# DIOT_Power_Supplies.net
KiCad netlist of a schematic drawn in Altium Designer
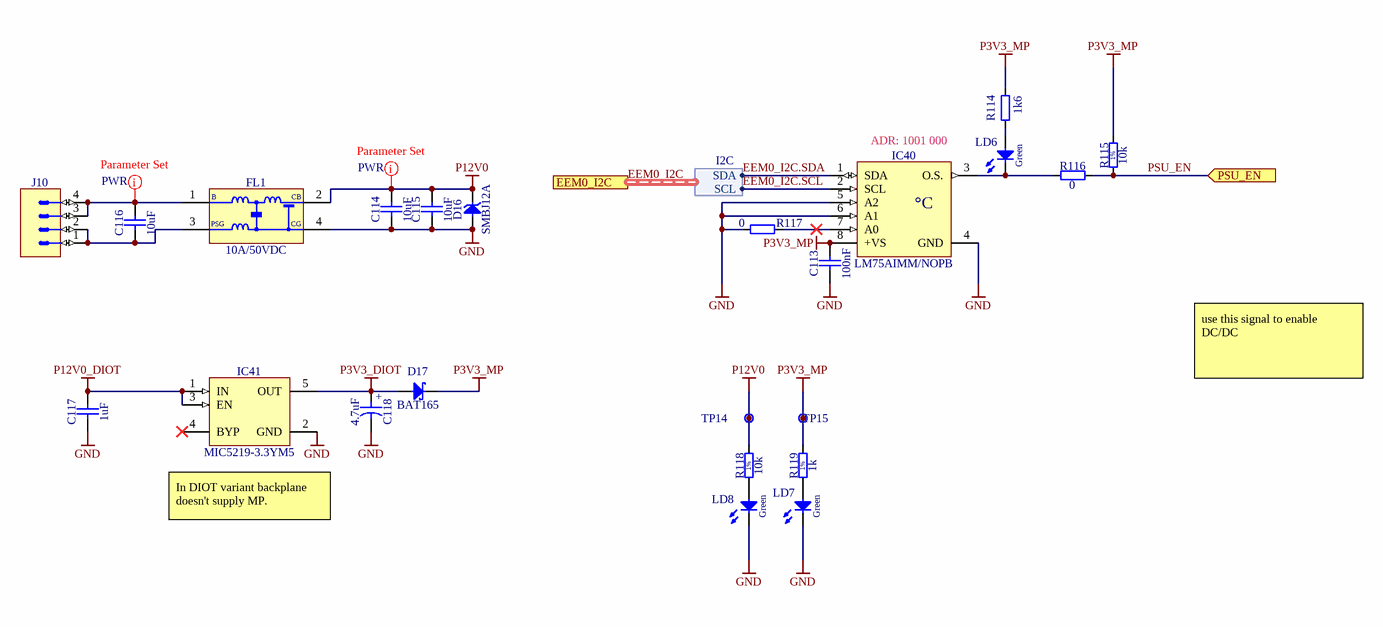
[diagram p0: DIOT_Power_Supplies.SchDoc]

(export (version "E")
  (design (tool "Eeschema 10.0.6"))
  (components
    (comp (ref "C113")
      (value "100nF")
      (footprint "CAPC1005X55N")
      (description "Non-polarised capacitor")
      (fields
        (field (name "PART NUMBER") "CC0402_100NF_16V_10%_X5R")
        (field (name "VOLTAGE") "16V")
        (field (name "AUTHOR") "CERN DEM JLC")
      )
      (libsource (lib "Capacitors") (part "Capacitor - non polarized"))
    )
    (comp (ref "C114")
      (value "10uF")
      (footprint "CAPC2012X95N")
      (description "Non-polarised capacitor")
      (fields
        (field (name "PART NUMBER") "CC0805_10UF_25V_10%_X5R")
        (field (name "VOLTAGE") "25V")
        (field (name "AUTHOR") "CERN DEM JLC")
      )
      (libsource (lib "Capacitors") (part "Capacitor - non polarized"))
    )
    (comp (ref "C115")
      (value "10uF")
      (footprint "CAPC2012X95N")
      (description "Non-polarised capacitor")
      (fields
        (field (name "PART NUMBER") "CC0805_10UF_25V_10%_X5R")
        (field (name "VOLTAGE") "25V")
        (field (name "AUTHOR") "CERN DEM JLC")
      )
      (libsource (lib "Capacitors") (part "Capacitor - non polarized"))
    )
    (comp (ref "C116")
      (value "10uF")
      (footprint "CAPC2012X95N")
      (description "Non-polarised capacitor")
      (fields
        (field (name "PART NUMBER") "CC0805_10UF_25V_10%_X5R")
        (field (name "VOLTAGE") "25V")
        (field (name "AUTHOR") "CERN DEM JLC")
      )
      (libsource (lib "Capacitors") (part "Capacitor - non polarized"))
    )
    (comp (ref "C117")
      (value "1uF")
      (footprint "CAPC1608X87N")
      (description "Non-polarised capacitor")
      (fields
        (field (name "PART NUMBER") "CC0603_1UF_25V_10%_X7R")
        (field (name "VOLTAGE") "25V")
        (field (name "AUTHOR") "CERN DEM JLC")
      )
      (libsource (lib "Capacitors") (part "Capacitor - non polarized"))
    )
    (comp (ref "C118")
      (value "4.7uF")
      (footprint "CAPMP3216X180N")
      (description "Polarised capacitor")
      (fields
        (field (name "PART NUMBER") "CTE3216-18_4.7UF_10V_10%_AVX_TPSA475K010T1400")
        (field (name "VOLTAGE") "10V")
        (field (name "AUTHOR") "CERN DEM JLC")
      )
      (libsource (lib "Capacitors") (part "Capacitor - polarized"))
    )
    (comp (ref "D16")
      (value "SMBJ12A")
      (footprint "DIOM5336X265N")
      (description "Zener Diode")
      (fields
        (field (name "VOLTAGE") "12V")
        (field (name "POWER") "600W")
        (field (name "AUTHOR") "CERN DEM JLC")
      )
      (libsource (lib "ICs And Semiconductors") (part "Diode Zener"))
    )
    (comp (ref "D17")
      (value "BAT165")
      (footprint "SOD2512X110N")
      (description "Schottky Diode")
      (fields
        (field (name "MANUFACTURER") "INFINEON")
        (field (name "VOLTAGE") "40V")
        (field (name "AUTHOR") "CERN DEM JLC")
      )
      (libsource (lib "ICs And Semiconductors") (part "Diode Schottky"))
    )
    (comp (ref "FL1")
      (value "10A/50VDC")
      (footprint "FIL_MURATA_BNX02")
      (description "Block Type EMIFIL (LC Combined)")
      (fields
        (field (name "PART NUMBER") "FIL_MURATA_BNX022-01L")
        (field (name "MANUFACTURER") "MURATA")
        (field (name "AUTHOR") "CERN DEM JLC")
      )
      (libsource (lib "Inductors & Transformers") (part "FIL_MURATA_BNX02"))
    )
    (comp (ref "IC40")
      (value "LM75AIMM/NOPB")
      (footprint "SOP65P490X109-8N")
      (description "Digital Temperature Sensor and Thermal Watchdog with Two-Wire Interface")
      (fields (field (name "MANUFACTURER") "TEXAS INSTRUMENTS") (field (name "AUTHOR") "CERN DEM JLC"))
      (libsource (lib "ICs And Semiconductors") (part "LM75"))
    )
    (comp (ref "IC41")
      (value "MIC5219-3.3YM5")
      (footprint "SOT95P280X145-5N")
      (description "500mA Peak Output LDO Regulator")
      (fields (field (name "MANUFACTURER") "MICROCHIP TECHNOLOGY") (field (name "AUTHOR") "CERN DEM WB"))
      (libsource (lib "ICs And Semiconductors") (part "MIC5219-X.XYM5"))
    )
    (comp (ref "J10")
      (value "Mini-Fit Jr.™")
      (footprint "MOLEX_39-30-0040")
      (description "Connector 4 Male")
      (fields
        (field (name "PART NUMBER") "MOLEX_39-30-0040")
        (field (name "MANUFACTURER") "MOLEX")
        (field (name "AUTHOR") "CERN DEM JLC")
      )
      (libsource (lib "Connectors") (part "Connector 4 Male"))
    )
    (comp (ref "LD6")
      (value "Green")
      (footprint "LED_KINGBRIGHT_KPH-1608CGCK")
      (description "LED Green 1C 2A")
      (fields
        (field (name "MANUFACTURER PART NUMBER") "KPH-1608CGCK")
        (field (name "PART NUMBER") "LED_KINGBRIGHT_KPH-1608CGCK")
        (field (name "AUTHOR") "CERN DEM JLC")
      )
      (libsource (lib "ICs And Semiconductors") (part "LED Green 1C 2A"))
    )
    (comp (ref "LD7")
      (value "Green")
      (footprint "LED_KINGBRIGHT_KPH-1608CGCK")
      (description "LED Green 1C 2A")
      (fields
        (field (name "MANUFACTURER PART NUMBER") "KPH-1608CGCK")
        (field (name "PART NUMBER") "LED_KINGBRIGHT_KPH-1608CGCK")
        (field (name "AUTHOR") "CERN DEM JLC")
      )
      (libsource (lib "ICs And Semiconductors") (part "LED Green 1C 2A"))
    )
    (comp (ref "LD8")
      (value "Green")
      (footprint "LED_KINGBRIGHT_KPH-1608CGCK")
      (description "LED Green 1C 2A")
      (fields
        (field (name "MANUFACTURER PART NUMBER") "KPH-1608CGCK")
        (field (name "PART NUMBER") "LED_KINGBRIGHT_KPH-1608CGCK")
        (field (name "AUTHOR") "CERN DEM JLC")
      )
      (libsource (lib "ICs And Semiconductors") (part "LED Green 1C 2A"))
    )
    (comp (ref "R114")
      (value "1k6")
      (footprint "RESC1005X40N")
      (description "Resistor - 1%")
      (fields
        (field (name "PART NUMBER") "R0402_1K6_1%_0.0625W_100PPM")
        (field (name "POWER") "0.0625W")
        (field (name "AUTHOR") "CERN DEM JLC")
      )
      (libsource (lib "Resistors") (part "Resistor - 1%"))
    )
    (comp (ref "R115")
      (value "10k")
      (footprint "RESC1005X40N")
      (description "Resistor - 1%")
      (fields
        (field (name "PART NUMBER") "R0402_10K_1%_0.0625W_100PPM")
        (field (name "POWER") "0.0625W")
        (field (name "AUTHOR") "CERN DEM JLC")
      )
      (libsource (lib "Resistors") (part "Resistor - 1%"))
    )
    (comp (ref "R116")
      (value "0")
      (footprint "RESC1005X40N")
      (description "Resistor")
      (fields
        (field (name "PART NUMBER") "R0402_0R_JUMPER")
        (field (name "MANUFACTURER") "GENERIC")
        (field (name "AUTHOR") "CERN DEM JLC")
      )
      (libsource (lib "Resistors") (part "Resistor"))
    )
    (comp (ref "R117")
      (value "0")
      (footprint "RESC1005X40N")
      (description "Resistor")
      (fields
        (field (name "PART NUMBER") "R0402_0R_JUMPER")
        (field (name "MANUFACTURER") "GENERIC")
        (field (name "AUTHOR") "CERN DEM JLC")
      )
      (libsource (lib "Resistors") (part "Resistor"))
    )
    (comp (ref "R118")
      (value "10k")
      (footprint "RESC1005X40N")
      (description "Resistor - 1%")
      (fields
        (field (name "PART NUMBER") "R0402_10K_1%_0.0625W_100PPM")
        (field (name "POWER") "0.0625W")
        (field (name "AUTHOR") "CERN DEM JLC")
      )
      (libsource (lib "Resistors") (part "Resistor - 1%"))
    )
    (comp (ref "R119")
      (value "1k")
      (footprint "RESC1005X40N")
      (description "Resistor - 1%")
      (fields
        (field (name "PART NUMBER") "R0402_1K_1%_0.0625W_100PPM")
        (field (name "POWER") "0.0625W")
        (field (name "AUTHOR") "CERN DEM JLC")
      )
      (libsource (lib "Resistors") (part "Resistor - 1%"))
    )
    (comp (ref "TP14")
      (value "P12V0")
      (footprint "TPS127")
      (description "Test Point")
      (fields (field (name "PART NUMBER") "SMD_PAD_1.27X1.27MM") (field (name "AUTHOR") "CERN DEM JLC"))
      (libsource (lib "Eletro-mechanical") (part "Test Point"))
    )
    (comp (ref "TP15")
      (value "P3V3")
      (footprint "TPS127")
      (description "Test Point")
      (fields (field (name "PART NUMBER") "SMD_PAD_1.27X1.27MM") (field (name "AUTHOR") "CERN DEM JLC"))
      (libsource (lib "Eletro-mechanical") (part "Test Point"))
    )
  )
  (nets
    (net (code "2") (name "/EEM0_I2C.SCL") (class "Default")
      (node (ref "IC40") (pin "2") (pinfunction "SCL_2") (pintype "input"))
    )
    (net (code "3") (name "/EEM0_I2C.SDA") (class "Default")
      (node (ref "IC40") (pin "1") (pinfunction "SDA_1") (pintype "bidirectional"))
    )
    (net (code "5") (name "/PSU_EN") (class "Default")
      (node (ref "R115") (pin "1") (pinfunction "1_1") (pintype "passive"))
      (node (ref "R116") (pin "2") (pinfunction "2_2") (pintype "passive"))
    )
    (net (code "6") (name "GND") (class "Default")
      (node (ref "C113") (pin "1") (pinfunction "1_1") (pintype "passive"))
      (node (ref "C114") (pin "1") (pinfunction "1_1") (pintype "passive"))
      (node (ref "C115") (pin "1") (pinfunction "1_1") (pintype "passive"))
      (node (ref "C117") (pin "1") (pinfunction "1_1") (pintype "passive"))
      (node (ref "C118") (pin "2") (pinfunction "2_2") (pintype "passive"))
      (node (ref "D16") (pin "2") (pinfunction "A_2") (pintype "passive"))
      (node (ref "FL1") (pin "4") (pinfunction "CG_4") (pintype "passive"))
      (node (ref "IC40") (pin "4") (pinfunction "GND_4") (pintype "power_in"))
      (node (ref "IC40") (pin "5") (pinfunction "A2_5") (pintype "input"))
      (node (ref "IC40") (pin "6") (pinfunction "A1_6") (pintype "input"))
      (node (ref "IC41") (pin "2") (pinfunction "GND_2") (pintype "power_in"))
      (node (ref "LD7") (pin "1") (pinfunction "C_1") (pintype "passive"))
      (node (ref "LD8") (pin "1") (pinfunction "C_1") (pintype "passive"))
      (node (ref "R117") (pin "1") (pinfunction "1_1") (pintype "passive"))
    )
    (net (code "7") (name "Net-(FL1-B)") (class "Default")
      (node (ref "C116") (pin "2") (pinfunction "2_2") (pintype "passive"))
      (node (ref "FL1") (pin "1") (pinfunction "B_1") (pintype "passive"))
      (node (ref "J10") (pin "3") (pinfunction "3_3") (pintype "bidirectional"))
      (node (ref "J10") (pin "4") (pinfunction "4_4") (pintype "bidirectional"))
    )
    (net (code "8") (name "Net-(FL1-PSG)") (class "Default")
      (node (ref "C116") (pin "1") (pinfunction "1_1") (pintype "passive"))
      (node (ref "FL1") (pin "3") (pinfunction "PSG_3") (pintype "passive"))
      (node (ref "J10") (pin "1") (pinfunction "1_1") (pintype "bidirectional"))
      (node (ref "J10") (pin "2") (pinfunction "2_2") (pintype "bidirectional"))
    )
    (net (code "9") (name "Net-(IC40-A0)") (class "Default")
      (node (ref "IC40") (pin "7") (pinfunction "A0_7") (pintype "input"))
      (node (ref "R117") (pin "2") (pinfunction "2_2") (pintype "passive"))
    )
    (net (code "10") (name "Net-(IC40-O.S.)") (class "Default")
      (node (ref "IC40") (pin "3") (pinfunction "O.S._3") (pintype "output"))
      (node (ref "LD6") (pin "1") (pinfunction "C_1") (pintype "passive"))
      (node (ref "R116") (pin "1") (pinfunction "1_1") (pintype "passive"))
    )
    (net (code "11") (name "Net-(LD6-A)") (class "Default")
      (node (ref "LD6") (pin "2") (pinfunction "A_2") (pintype "passive"))
      (node (ref "R114") (pin "1") (pinfunction "1_1") (pintype "passive"))
    )
    (net (code "12") (name "Net-(LD7-A)") (class "Default")
      (node (ref "LD7") (pin "2") (pinfunction "A_2") (pintype "passive"))
      (node (ref "R119") (pin "1") (pinfunction "1_1") (pintype "passive"))
    )
    (net (code "13") (name "Net-(LD8-A)") (class "Default")
      (node (ref "LD8") (pin "2") (pinfunction "A_2") (pintype "passive"))
      (node (ref "R118") (pin "1") (pinfunction "1_1") (pintype "passive"))
    )
    (net (code "14") (name "P3V3_DIOT") (class "Default")
      (node (ref "C118") (pin "1") (pinfunction "1_1") (pintype "passive"))
      (node (ref "D17") (pin "2") (pinfunction "A_2") (pintype "passive"))
      (node (ref "IC41") (pin "5") (pinfunction "OUT_5") (pintype "power_in"))
    )
    (net (code "15") (name "P3V3_MP") (class "Default")
      (node (ref "C113") (pin "2") (pinfunction "2_2") (pintype "passive"))
      (node (ref "D17") (pin "1") (pinfunction "C_1") (pintype "passive"))
      (node (ref "IC40") (pin "8") (pinfunction "+VS_8") (pintype "power_in"))
      (node (ref "R114") (pin "2") (pinfunction "2_2") (pintype "passive"))
      (node (ref "R115") (pin "2") (pinfunction "2_2") (pintype "passive"))
      (node (ref "R119") (pin "2") (pinfunction "2_2") (pintype "passive"))
      (node (ref "TP15") (pin "1") (pinfunction "1_1") (pintype "bidirectional"))
    )
    (net (code "16") (name "P12V0") (class "Default")
      (node (ref "C114") (pin "2") (pinfunction "2_2") (pintype "passive"))
      (node (ref "C115") (pin "2") (pinfunction "2_2") (pintype "passive"))
      (node (ref "D16") (pin "1") (pinfunction "C_1") (pintype "passive"))
      (node (ref "FL1") (pin "2") (pinfunction "CB_2") (pintype "passive"))
      (node (ref "R118") (pin "2") (pinfunction "2_2") (pintype "passive"))
      (node (ref "TP14") (pin "1") (pinfunction "1_1") (pintype "bidirectional"))
    )
    (net (code "17") (name "P12V0_DIOT") (class "Default")
      (node (ref "C117") (pin "2") (pinfunction "2_2") (pintype "passive"))
      (node (ref "IC41") (pin "1") (pinfunction "IN_1") (pintype "input"))
      (node (ref "IC41") (pin "3") (pinfunction "EN_3") (pintype "input"))
    )
    (net (code "18") (name "unconnected-(IC41-BYP-Pad4)") (class "Default")
      (node (ref "IC41") (pin "4") (pinfunction "BYP_4") (pintype "passive+no_connect"))
    )
  )
)
